# SCH_DongleHub_2024-06-30_1.net
KiCad netlist of a schematic drawn in EasyEDA
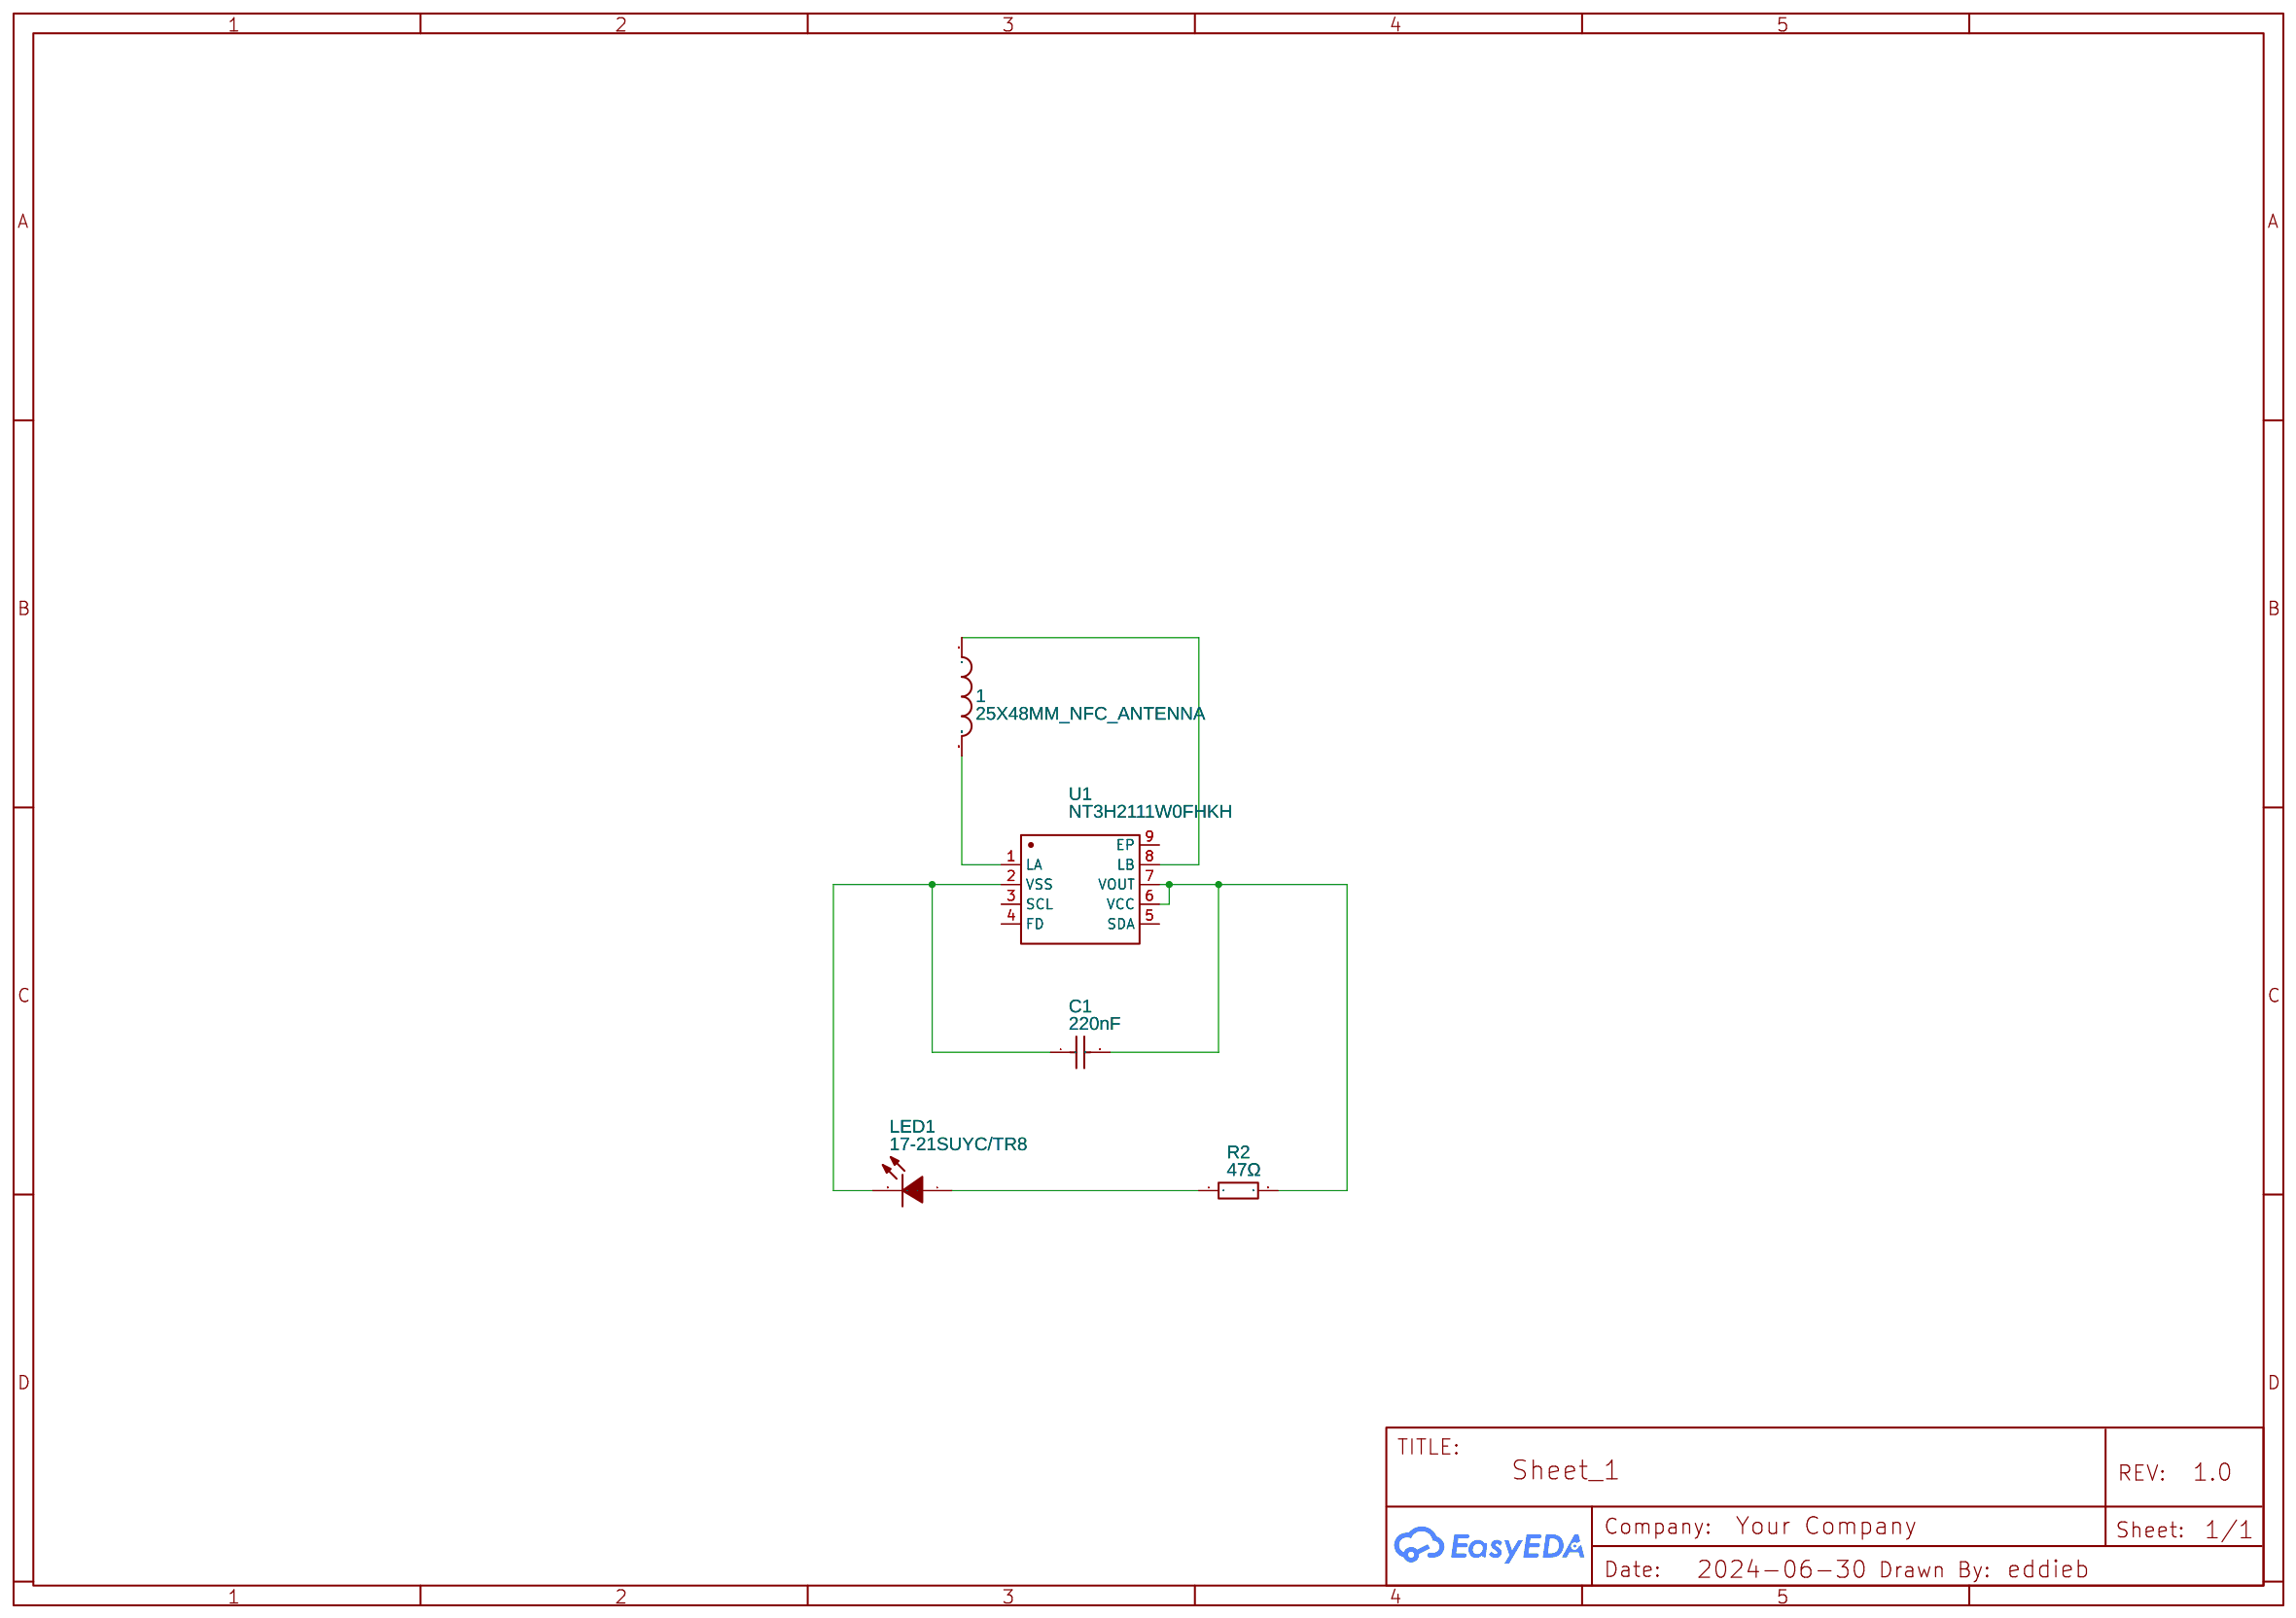
[diagram p0: schematic sheet]

(export (version "E")
  (design (tool "Eeschema 10.0.6"))
  (components
    (comp (ref "1") (value "25X48MM_NFC_ANTENNA") (libsource (lib "") (part "25X48MM_NFC_ANTENNA")))
    (comp (ref "C1")
      (value "220nF")
      (fields
        (field (name "Manufacturer Part") "CL10B224KA8NNNC")
        (field (name "Manufacturer") "SAMSUNG(三星)")
      )
      (libsource (lib "") (part "CL10B224KA8NNNC"))
    )
    (comp (ref "LED1")
      (value "17-21SUYC/TR8")
      (fields (field (name "Manufacturer Part") "KT-0805黄灯") (field (name "Manufacturer") "KENTO"))
      (libsource (lib "") (part "17-21SUYC/TR8"))
    )
    (comp (ref "R2")
      (value "47Ω")
      (fields
        (field (name "Manufacturer Part") "0603WAF470JT5E")
        (field (name "Manufacturer") "UNI-ROYAL(厚声)")
      )
      (libsource (lib "") (part "0603WAF470JT5E"))
    )
    (comp (ref "U1")
      (value "NT3H2111W0FHKH")
      (fields (field (name "Manufacturer") "NXP(恩智浦)"))
      (libsource (lib "") (part "NT3H2111W0FHKH"))
    )
  )
  (nets
    (net (code "1") (name "Net-(LED1-+)") (class "Default")
      (node (ref "LED1") (pin "1") (pinfunction "+_1") (pintype "unspecified"))
      (node (ref "R2") (pin "1") (pinfunction "1_1") (pintype "input"))
    )
    (net (code "2") (name "Net-(LED1--)") (class "Default")
      (node (ref "C1") (pin "1") (pinfunction "1_1") (pintype "input"))
      (node (ref "LED1") (pin "2") (pinfunction "-_2") (pintype "unspecified"))
      (node (ref "U1") (pin "2") (pinfunction "VSS_2") (pintype "unspecified"))
    )
    (net (code "3") (name "Net-(U1-LA)") (class "Default")
      (node (ref "1") (pin "P$2") (pinfunction "P$2_P$2") (pintype "bidirectional"))
      (node (ref "U1") (pin "1") (pinfunction "LA_1") (pintype "unspecified"))
    )
    (net (code "4") (name "Net-(U1-LB)") (class "Default")
      (node (ref "1") (pin "P$1") (pinfunction "P$1_P$1") (pintype "bidirectional"))
      (node (ref "U1") (pin "8") (pinfunction "LB_8") (pintype "unspecified"))
    )
    (net (code "5") (name "Net-(U1-VCC)") (class "Default")
      (node (ref "C1") (pin "2") (pinfunction "2_2") (pintype "input"))
      (node (ref "R2") (pin "2") (pinfunction "2_2") (pintype "input"))
      (node (ref "U1") (pin "6") (pinfunction "VCC_6") (pintype "unspecified"))
      (node (ref "U1") (pin "7") (pinfunction "VOUT_7") (pintype "unspecified"))
    )
    (net (code "6") (name "unconnected-(U1-EP-Pad9)") (class "Default")
      (node (ref "U1") (pin "9") (pinfunction "EP_9") (pintype "unspecified"))
    )
    (net (code "7") (name "unconnected-(U1-FD-Pad4)") (class "Default")
      (node (ref "U1") (pin "4") (pinfunction "FD_4") (pintype "unspecified"))
    )
    (net (code "8") (name "unconnected-(U1-SCL-Pad3)") (class "Default")
      (node (ref "U1") (pin "3") (pinfunction "SCL_3") (pintype "unspecified"))
    )
    (net (code "9") (name "unconnected-(U1-SDA-Pad5)") (class "Default")
      (node (ref "U1") (pin "5") (pinfunction "SDA_5") (pintype "unspecified"))
    )
  )
)
